# APD9328_ETHERNET.net
KiCad netlist of a schematic drawn in Altium Designer
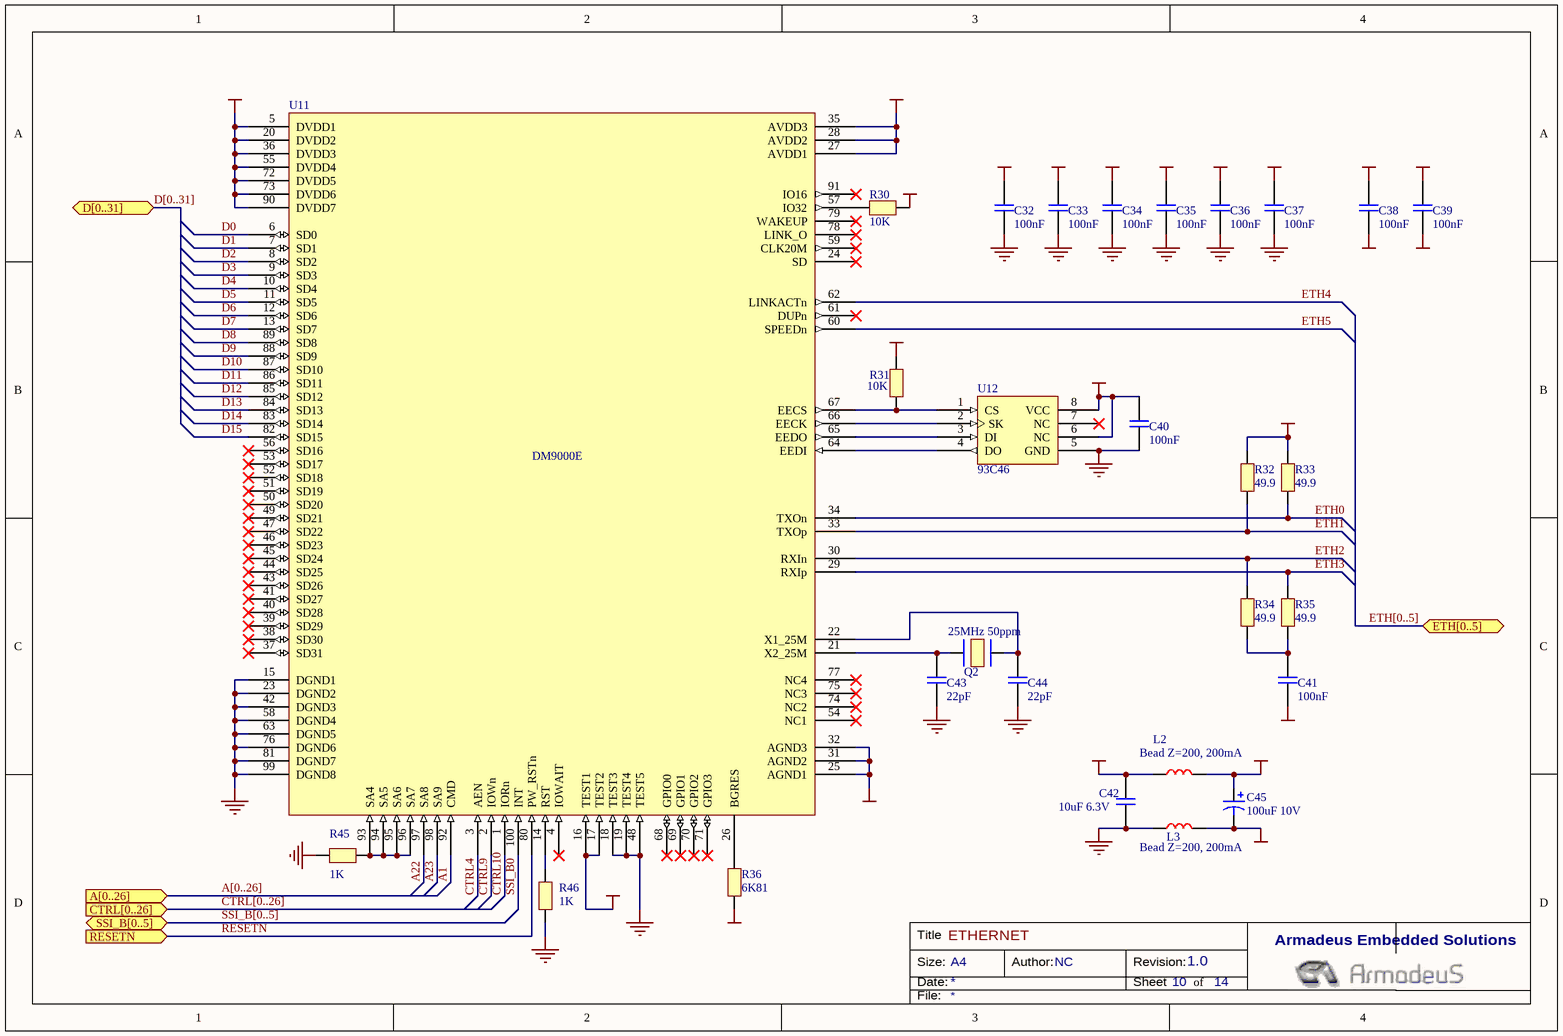
[diagram p0: APD9328_ETHERNET.SchDoc]

(export (version "E")
  (design (tool "Eeschema 10.0.6"))
  (components
    (comp (ref "C32")
      (value "100nF")
      (footprint "0402")
      (fields (field (name "MANUFACTURER") "Kemet") (field (name "PART NUMBER") "C0402C104K8RACTU"))
      (libsource (lib "Misc") (part "Cap"))
    )
    (comp (ref "C33") (value "100nF") (footprint "0402") (libsource (lib "Misc") (part "Cap")))
    (comp (ref "C34") (value "100nF") (footprint "0402") (libsource (lib "Misc") (part "Cap")))
    (comp (ref "C35") (value "100nF") (footprint "0402") (libsource (lib "Misc") (part "Cap")))
    (comp (ref "C36") (value "100nF") (footprint "0402") (libsource (lib "Misc") (part "Cap")))
    (comp (ref "C37") (value "100nF") (footprint "0402") (libsource (lib "Misc") (part "Cap")))
    (comp (ref "C38") (value "100nF") (footprint "0402") (libsource (lib "Misc") (part "Cap")))
    (comp (ref "C39") (value "100nF") (footprint "0402") (libsource (lib "Misc") (part "Cap")))
    (comp (ref "C40") (value "100nF") (footprint "0402") (libsource (lib "Misc") (part "Cap")))
    (comp (ref "C41") (value "100nF") (footprint "0402") (libsource (lib "Misc") (part "Cap")))
    (comp (ref "C42")
      (value "10uF 6.3V")
      (footprint "0805")
      (description "Cermaic Capacitor")
      (fields (field (name "MANUFACTURER") "Kemet") (field (name "PART NUMBER") "C0805C106K9PAC7800"))
      (libsource (lib "Misc") (part "Cap"))
    )
    (comp (ref "C43") (value "22pF") (footprint "0402") (libsource (lib "Misc") (part "Cap")))
    (comp (ref "C44") (value "22pF") (footprint "0402") (libsource (lib "Misc") (part "Cap")))
    (comp (ref "C45")
      (value "100uF 10V")
      (footprint "D")
      (description "Solid Tantalum Chip Capacitor, Standard T491 Series - Industrial Grade")
      (fields
        (field (name "MANUFACTURER") "Kemet")
        (field (name "PART NUMBER") "T491D107K006AS")
        (field (name "PUBLISHER") "Altium Limited")
      )
      (libsource (lib "KEMET Chip Capacitor") (part "T491D"))
    )
    (comp (ref "L2")
      (value "Bead Z=200, 200mA")
      (footprint "0603")
      (description "Bead")
      (fields (field (name "MANUFACTURER") "Murata") (field (name "PART NUMBER") "BLM18AG221SN1"))
      (libsource (lib "*") (part "Self"))
    )
    (comp (ref "L3")
      (value "Bead Z=200, 200mA")
      (footprint "0603")
      (fields (field (name "MANUFACTURER") "Murata") (field (name "PART NUMBER") "BLM18AG221SN1"))
      (libsource (lib "*") (part "Self"))
    )
    (comp (ref "Q2")
      (value "25MHz 50ppm")
      (description "Quartz")
      (fields (field (name "MANUFACTURER") "ECS") (field (name "PART NUMBER") "ECS-250-18-5P"))
      (libsource (lib "*") (part "QUARTZ"))
    )
    (comp (ref "R30") (value "10K") (footprint "0402") (libsource (lib "") (part "Res_2")))
    (comp (ref "R31") (value "10K") (footprint "0402") (libsource (lib "") (part "Res_1")))
    (comp (ref "R32") (value "49.9") (footprint "0402") (libsource (lib "") (part "Res_1")))
    (comp (ref "R33") (value "49.9") (footprint "0402") (libsource (lib "") (part "Res_1")))
    (comp (ref "R34") (value "49.9") (footprint "0402") (libsource (lib "") (part "Res_1")))
    (comp (ref "R35") (value "49.9") (footprint "0402") (libsource (lib "") (part "Res_1")))
    (comp (ref "R36") (value "6K81") (footprint "0402") (libsource (lib "") (part "Res_1")))
    (comp (ref "R45") (value "1K") (footprint "0402") (libsource (lib "*") (part "Res")))
    (comp (ref "R46") (value "1K") (footprint "0402") (libsource (lib "") (part "Res_1")))
    (comp (ref "U11")
      (value "DM9000E")
      (footprint "LQFP100")
      (description "Ethernet Single Chip")
      (fields (field (name "MANUFACTURER") "Davicom"))
      (libsource (lib "Armadeus") (part "DM9000"))
    )
    (comp (ref "U12")
      (value "93C46")
      (footprint "MSOP8")
      (description "Serial Microwire EEPROM")
      (fields (field (name "MANUFACTURER") "Microchip") (field (name "PART NUMBER") "93LC46B-I/MS"))
      (libsource (lib "Armadeus") (part "93C46"))
    )
  )
  (nets
    (net (code "70") (name "+3V3") (class "Default")
      (node (ref "C32") (pin "1") (pintype "passive"))
      (node (ref "C33") (pin "1") (pintype "passive"))
      (node (ref "C34") (pin "1") (pintype "passive"))
      (node (ref "C35") (pin "1") (pintype "passive"))
      (node (ref "C36") (pin "1") (pintype "passive"))
      (node (ref "C37") (pin "1") (pintype "passive"))
      (node (ref "C40") (pin "1") (pintype "passive"))
      (node (ref "C42") (pin "2") (pintype "passive"))
      (node (ref "L2") (pin "1") (pintype "passive"))
      (node (ref "R30") (pin "2") (pintype "passive"))
      (node (ref "R31") (pin "2") (pintype "passive"))
      (node (ref "U11") (pin "16") (pinfunction "TEST1_16") (pintype "input"))
      (node (ref "U11") (pin "17") (pinfunction "TEST2_17") (pintype "input"))
      (node (ref "U11") (pin "20") (pinfunction "DVDD2_20") (pintype "power_in"))
      (node (ref "U11") (pin "36") (pinfunction "DVDD3_36") (pintype "power_in"))
      (node (ref "U11") (pin "5") (pinfunction "DVDD1_5") (pintype "power_in"))
      (node (ref "U11") (pin "55") (pinfunction "DVDD4_55") (pintype "power_in"))
      (node (ref "U11") (pin "72") (pinfunction "DVDD5_72") (pintype "power_in"))
      (node (ref "U11") (pin "73") (pinfunction "DVDD6_73") (pintype "power_in"))
      (node (ref "U11") (pin "90") (pinfunction "DVDD7_90") (pintype "power_in"))
      (node (ref "U12") (pin "6") (pinfunction "NC_6") (pintype "passive"))
      (node (ref "U12") (pin "8") (pinfunction "VCC_8") (pintype "power_in"))
    )
    (net (code "71") (name "/A1") (class "Default")
      (node (ref "U11") (pin "92") (pinfunction "CMD_92") (pintype "input"))
    )
    (net (code "72") (name "/A22") (class "Default")
      (node (ref "U11") (pin "97") (pinfunction "SA8_97") (pintype "input"))
    )
    (net (code "73") (name "/A23") (class "Default")
      (node (ref "U11") (pin "98") (pinfunction "SA9_98") (pintype "input"))
    )
    (net (code "75") (name "/CTRL4") (class "Default")
      (node (ref "U11") (pin "3") (pinfunction "AEN_3") (pintype "input"))
    )
    (net (code "76") (name "/CTRL9") (class "Default")
      (node (ref "U11") (pin "2") (pinfunction "IOWn_2") (pintype "input"))
    )
    (net (code "77") (name "/CTRL10") (class "Default")
      (node (ref "U11") (pin "1") (pinfunction "IORn_1") (pintype "input"))
    )
    (net (code "79") (name "/D0") (class "Default")
      (node (ref "U11") (pin "6") (pinfunction "SD0_6") (pintype "bidirectional"))
    )
    (net (code "80") (name "/D1") (class "Default")
      (node (ref "U11") (pin "7") (pinfunction "SD1_7") (pintype "bidirectional"))
    )
    (net (code "81") (name "/D2") (class "Default")
      (node (ref "U11") (pin "8") (pinfunction "SD2_8") (pintype "bidirectional"))
    )
    (net (code "82") (name "/D3") (class "Default")
      (node (ref "U11") (pin "9") (pinfunction "SD3_9") (pintype "bidirectional"))
    )
    (net (code "83") (name "/D4") (class "Default")
      (node (ref "U11") (pin "10") (pinfunction "SD4_10") (pintype "bidirectional"))
    )
    (net (code "84") (name "/D5") (class "Default")
      (node (ref "U11") (pin "11") (pinfunction "SD5_11") (pintype "bidirectional"))
    )
    (net (code "85") (name "/D6") (class "Default")
      (node (ref "U11") (pin "12") (pinfunction "SD6_12") (pintype "bidirectional"))
    )
    (net (code "86") (name "/D7") (class "Default")
      (node (ref "U11") (pin "13") (pinfunction "SD7_13") (pintype "bidirectional"))
    )
    (net (code "87") (name "/D8") (class "Default")
      (node (ref "U11") (pin "89") (pinfunction "SD8_89") (pintype "bidirectional"))
    )
    (net (code "88") (name "/D9") (class "Default")
      (node (ref "U11") (pin "88") (pinfunction "SD9_88") (pintype "bidirectional"))
    )
    (net (code "89") (name "/D10") (class "Default")
      (node (ref "U11") (pin "87") (pinfunction "SD10_87") (pintype "bidirectional"))
    )
    (net (code "90") (name "/D11") (class "Default")
      (node (ref "U11") (pin "86") (pinfunction "SD11_86") (pintype "bidirectional"))
    )
    (net (code "91") (name "/D12") (class "Default")
      (node (ref "U11") (pin "85") (pinfunction "SD12_85") (pintype "bidirectional"))
    )
    (net (code "92") (name "/D13") (class "Default")
      (node (ref "U11") (pin "84") (pinfunction "SD13_84") (pintype "bidirectional"))
    )
    (net (code "93") (name "/D14") (class "Default")
      (node (ref "U11") (pin "83") (pinfunction "SD14_83") (pintype "bidirectional"))
    )
    (net (code "94") (name "/D15") (class "Default")
      (node (ref "U11") (pin "82") (pinfunction "SD15_82") (pintype "bidirectional"))
    )
    (net (code "96") (name "/ETH0") (class "Default")
      (node (ref "R33") (pin "1") (pintype "passive"))
      (node (ref "U11") (pin "34") (pinfunction "TXOn_34") (pintype "passive"))
    )
    (net (code "97") (name "/ETH1") (class "Default")
      (node (ref "R32") (pin "1") (pintype "passive"))
      (node (ref "U11") (pin "33") (pinfunction "TXOp_33") (pintype "passive"))
    )
    (net (code "98") (name "/ETH2") (class "Default")
      (node (ref "R34") (pin "2") (pintype "passive"))
      (node (ref "U11") (pin "30") (pinfunction "RXIn_30") (pintype "passive"))
    )
    (net (code "99") (name "/ETH3") (class "Default")
      (node (ref "R35") (pin "2") (pintype "passive"))
      (node (ref "U11") (pin "29") (pinfunction "RXIp_29") (pintype "passive"))
    )
    (net (code "100") (name "/ETH4") (class "Default")
      (node (ref "U11") (pin "62") (pinfunction "LINKACTn_62") (pintype "output"))
    )
    (net (code "101") (name "/ETH5") (class "Default")
      (node (ref "U11") (pin "60") (pinfunction "SPEEDn_60") (pintype "output"))
    )
    (net (code "103") (name "/RESETN") (class "Default")
      (node (ref "U11") (pin "80") (pinfunction "PW_RSTn_80") (pintype "input"))
    )
    (net (code "104") (name "/SSI_B0") (class "Default")
      (node (ref "U11") (pin "100") (pinfunction "INT_100") (pintype "input"))
    )
    (net (code "106") (name "AGND") (class "Default")
      (node (ref "C38") (pin "2") (pintype "passive"))
      (node (ref "C39") (pin "2") (pintype "passive"))
      (node (ref "C41") (pin "1") (pintype "passive"))
      (node (ref "C45") (pin "2") (pinfunction "2_2") (pintype "passive"))
      (node (ref "L3") (pin "2") (pintype "passive"))
      (node (ref "R36") (pin "1") (pintype "passive"))
      (node (ref "U11") (pin "25") (pinfunction "AGND1_25") (pintype "power_in"))
      (node (ref "U11") (pin "31") (pinfunction "AGND2_31") (pintype "power_in"))
      (node (ref "U11") (pin "32") (pinfunction "AGND3_32") (pintype "power_in"))
    )
    (net (code "107") (name "AVDD") (class "Default")
      (node (ref "C38") (pin "1") (pintype "passive"))
      (node (ref "C39") (pin "1") (pintype "passive"))
      (node (ref "C45") (pin "1") (pinfunction "1_1") (pintype "passive"))
      (node (ref "L2") (pin "2") (pintype "passive"))
      (node (ref "R32") (pin "2") (pintype "passive"))
      (node (ref "R33") (pin "2") (pintype "passive"))
      (node (ref "U11") (pin "27") (pinfunction "AVDD1_27") (pintype "power_in"))
      (node (ref "U11") (pin "28") (pinfunction "AVDD2_28") (pintype "power_in"))
      (node (ref "U11") (pin "35") (pinfunction "AVDD3_35") (pintype "power_in"))
    )
    (net (code "108") (name "GND") (class "Default")
      (node (ref "C32") (pin "2") (pintype "passive"))
      (node (ref "C33") (pin "2") (pintype "passive"))
      (node (ref "C34") (pin "2") (pintype "passive"))
      (node (ref "C35") (pin "2") (pintype "passive"))
      (node (ref "C36") (pin "2") (pintype "passive"))
      (node (ref "C37") (pin "2") (pintype "passive"))
      (node (ref "C40") (pin "2") (pintype "passive"))
      (node (ref "C42") (pin "1") (pintype "passive"))
      (node (ref "C43") (pin "1") (pintype "passive"))
      (node (ref "C44") (pin "1") (pintype "passive"))
      (node (ref "L3") (pin "1") (pintype "passive"))
      (node (ref "R45") (pin "2") (pintype "passive"))
      (node (ref "R46") (pin "1") (pintype "passive"))
      (node (ref "U11") (pin "15") (pinfunction "DGND1_15") (pintype "power_in"))
      (node (ref "U11") (pin "18") (pinfunction "TEST3_18") (pintype "input"))
      (node (ref "U11") (pin "19") (pinfunction "TEST4_19") (pintype "input"))
      (node (ref "U11") (pin "23") (pinfunction "DGND2_23") (pintype "power_in"))
      (node (ref "U11") (pin "42") (pinfunction "DGND3_42") (pintype "power_in"))
      (node (ref "U11") (pin "48") (pinfunction "TEST5_48") (pintype "input"))
      (node (ref "U11") (pin "58") (pinfunction "DGND4_58") (pintype "power_in"))
      (node (ref "U11") (pin "63") (pinfunction "DGND5_63") (pintype "power_in"))
      (node (ref "U11") (pin "76") (pinfunction "DGND6_76") (pintype "power_in"))
      (node (ref "U11") (pin "81") (pinfunction "DGND7_81") (pintype "power_in"))
      (node (ref "U11") (pin "99") (pinfunction "DGND8_99") (pintype "power_in"))
      (node (ref "U12") (pin "5") (pinfunction "GND_5") (pintype "power_in"))
    )
    (net (code "109") (name "Net-(C41-Pad2)") (class "Default")
      (node (ref "C41") (pin "2") (pintype "passive"))
      (node (ref "R34") (pin "1") (pintype "passive"))
      (node (ref "R35") (pin "1") (pintype "passive"))
    )
    (net (code "110") (name "Net-(U11-BGRES)") (class "Default")
      (node (ref "R36") (pin "2") (pintype "passive"))
      (node (ref "U11") (pin "26") (pinfunction "BGRES_26") (pintype "passive"))
    )
    (net (code "111") (name "Net-(U11-EECK)") (class "Default")
      (node (ref "U11") (pin "66") (pinfunction "EECK_66") (pintype "output"))
      (node (ref "U12") (pin "2") (pinfunction "SK_2") (pintype "input"))
    )
    (net (code "112") (name "Net-(U11-EECS)") (class "Default")
      (node (ref "R31") (pin "1") (pintype "passive"))
      (node (ref "U11") (pin "67") (pinfunction "EECS_67") (pintype "output"))
      (node (ref "U12") (pin "1") (pinfunction "CS_1") (pintype "input"))
    )
    (net (code "113") (name "Net-(U11-EEDI)") (class "Default")
      (node (ref "U11") (pin "64") (pinfunction "EEDI_64") (pintype "input"))
      (node (ref "U12") (pin "4") (pinfunction "DO_4") (pintype "output"))
    )
    (net (code "114") (name "Net-(U11-EEDO)") (class "Default")
      (node (ref "U11") (pin "65") (pinfunction "EEDO_65") (pintype "output"))
      (node (ref "U12") (pin "3") (pinfunction "DI_3") (pintype "input"))
    )
    (net (code "115") (name "Net-(U11-IO32)") (class "Default")
      (node (ref "R30") (pin "1") (pintype "passive"))
      (node (ref "U11") (pin "57") (pinfunction "IO32_57") (pintype "output"))
    )
    (net (code "116") (name "Net-(U11-RST)") (class "Default")
      (node (ref "R46") (pin "2") (pintype "passive"))
      (node (ref "U11") (pin "14") (pinfunction "RST_14") (pintype "input"))
    )
    (net (code "117") (name "Net-(U11-SA4)") (class "Default")
      (node (ref "R45") (pin "1") (pintype "passive"))
      (node (ref "U11") (pin "93") (pinfunction "SA4_93") (pintype "input"))
      (node (ref "U11") (pin "94") (pinfunction "SA5_94") (pintype "input"))
      (node (ref "U11") (pin "95") (pinfunction "SA6_95") (pintype "input"))
      (node (ref "U11") (pin "96") (pinfunction "SA7_96") (pintype "input"))
    )
    (net (code "118") (name "Net-(U11-X1_25M)") (class "Default")
      (node (ref "C44") (pin "2") (pintype "passive"))
      (node (ref "Q2") (pin "2") (pintype "passive"))
      (node (ref "U11") (pin "22") (pinfunction "X1_25M_22") (pintype "passive"))
    )
    (net (code "119") (name "Net-(U11-X2_25M)") (class "Default")
      (node (ref "C43") (pin "2") (pintype "passive"))
      (node (ref "Q2") (pin "1") (pintype "passive"))
      (node (ref "U11") (pin "21") (pinfunction "X2_25M_21") (pintype "passive"))
    )
    (net (code "120") (name "unconnected-(U11-CLK20M-Pad59)") (class "Default")
      (node (ref "U11") (pin "59") (pinfunction "CLK20M_59") (pintype "output+no_connect"))
    )
    (net (code "121") (name "unconnected-(U11-DUPn-Pad61)") (class "Default")
      (node (ref "U11") (pin "61") (pinfunction "DUPn_61") (pintype "output+no_connect"))
    )
    (net (code "122") (name "unconnected-(U11-GPIO0-Pad68)") (class "Default")
      (node (ref "U11") (pin "68") (pinfunction "GPIO0_68") (pintype "bidirectional+no_connect"))
    )
    (net (code "123") (name "unconnected-(U11-GPIO1-Pad69)") (class "Default")
      (node (ref "U11") (pin "69") (pinfunction "GPIO1_69") (pintype "bidirectional+no_connect"))
    )
    (net (code "124") (name "unconnected-(U11-GPIO2-Pad70)") (class "Default")
      (node (ref "U11") (pin "70") (pinfunction "GPIO2_70") (pintype "bidirectional+no_connect"))
    )
    (net (code "125") (name "unconnected-(U11-GPIO3-Pad71)") (class "Default")
      (node (ref "U11") (pin "71") (pinfunction "GPIO3_71") (pintype "bidirectional+no_connect"))
    )
    (net (code "126") (name "unconnected-(U11-IO16-Pad91)") (class "Default")
      (node (ref "U11") (pin "91") (pinfunction "IO16_91") (pintype "output+no_connect"))
    )
    (net (code "127") (name "unconnected-(U11-IOWAIT-Pad4)") (class "Default")
      (node (ref "U11") (pin "4") (pinfunction "IOWAIT_4") (pintype "input+no_connect"))
    )
    (net (code "128") (name "unconnected-(U11-LINK_O-Pad78)") (class "Default")
      (node (ref "U11") (pin "78") (pinfunction "LINK_O_78") (pintype "passive+no_connect"))
    )
    (net (code "129") (name "unconnected-(U11-NC1-Pad54)") (class "Default")
      (node (ref "U11") (pin "54") (pinfunction "NC1_54") (pintype "passive+no_connect"))
    )
    (net (code "130") (name "unconnected-(U11-NC2-Pad74)") (class "Default")
      (node (ref "U11") (pin "74") (pinfunction "NC2_74") (pintype "passive+no_connect"))
    )
    (net (code "131") (name "unconnected-(U11-NC3-Pad75)") (class "Default")
      (node (ref "U11") (pin "75") (pinfunction "NC3_75") (pintype "passive+no_connect"))
    )
    (net (code "132") (name "unconnected-(U11-NC4-Pad77)") (class "Default")
      (node (ref "U11") (pin "77") (pinfunction "NC4_77") (pintype "passive+no_connect"))
    )
    (net (code "133") (name "unconnected-(U11-SD-Pad24)") (class "Default")
      (node (ref "U11") (pin "24") (pinfunction "SD_24") (pintype "passive+no_connect"))
    )
    (net (code "134") (name "unconnected-(U11-SD16-Pad56)") (class "Default")
      (node (ref "U11") (pin "56") (pinfunction "SD16_56") (pintype "bidirectional+no_connect"))
    )
    (net (code "135") (name "unconnected-(U11-SD17-Pad53)") (class "Default")
      (node (ref "U11") (pin "53") (pinfunction "SD17_53") (pintype "bidirectional+no_connect"))
    )
    (net (code "136") (name "unconnected-(U11-SD18-Pad52)") (class "Default")
      (node (ref "U11") (pin "52") (pinfunction "SD18_52") (pintype "bidirectional+no_connect"))
    )
    (net (code "137") (name "unconnected-(U11-SD19-Pad51)") (class "Default")
      (node (ref "U11") (pin "51") (pinfunction "SD19_51") (pintype "bidirectional+no_connect"))
    )
    (net (code "138") (name "unconnected-(U11-SD20-Pad50)") (class "Default")
      (node (ref "U11") (pin "50") (pinfunction "SD20_50") (pintype "bidirectional+no_connect"))
    )
    (net (code "139") (name "unconnected-(U11-SD21-Pad49)") (class "Default")
      (node (ref "U11") (pin "49") (pinfunction "SD21_49") (pintype "bidirectional+no_connect"))
    )
    (net (code "140") (name "unconnected-(U11-SD22-Pad47)") (class "Default")
      (node (ref "U11") (pin "47") (pinfunction "SD22_47") (pintype "bidirectional+no_connect"))
    )
    (net (code "141") (name "unconnected-(U11-SD23-Pad46)") (class "Default")
      (node (ref "U11") (pin "46") (pinfunction "SD23_46") (pintype "bidirectional+no_connect"))
    )
    (net (code "142") (name "unconnected-(U11-SD24-Pad45)") (class "Default")
      (node (ref "U11") (pin "45") (pinfunction "SD24_45") (pintype "bidirectional+no_connect"))
    )
    (net (code "143") (name "unconnected-(U11-SD25-Pad44)") (class "Default")
      (node (ref "U11") (pin "44") (pinfunction "SD25_44") (pintype "bidirectional+no_connect"))
    )
    (net (code "144") (name "unconnected-(U11-SD26-Pad43)") (class "Default")
      (node (ref "U11") (pin "43") (pinfunction "SD26_43") (pintype "bidirectional+no_connect"))
    )
    (net (code "145") (name "unconnected-(U11-SD27-Pad41)") (class "Default")
      (node (ref "U11") (pin "41") (pinfunction "SD27_41") (pintype "bidirectional+no_connect"))
    )
    (net (code "146") (name "unconnected-(U11-SD28-Pad40)") (class "Default")
      (node (ref "U11") (pin "40") (pinfunction "SD28_40") (pintype "bidirectional+no_connect"))
    )
    (net (code "147") (name "unconnected-(U11-SD29-Pad39)") (class "Default")
      (node (ref "U11") (pin "39") (pinfunction "SD29_39") (pintype "bidirectional+no_connect"))
    )
    (net (code "148") (name "unconnected-(U11-SD30-Pad38)") (class "Default")
      (node (ref "U11") (pin "38") (pinfunction "SD30_38") (pintype "bidirectional+no_connect"))
    )
    (net (code "149") (name "unconnected-(U11-SD31-Pad37)") (class "Default")
      (node (ref "U11") (pin "37") (pinfunction "SD31_37") (pintype "bidirectional+no_connect"))
    )
    (net (code "150") (name "unconnected-(U11-WAKEUP-Pad79)") (class "Default")
      (node (ref "U11") (pin "79") (pinfunction "WAKEUP_79") (pintype "passive+no_connect"))
    )
    (net (code "151") (name "unconnected-(U12-NC-Pad7)") (class "Default")
      (node (ref "U12") (pin "7") (pinfunction "NC_7") (pintype "passive+no_connect"))
    )
  )
)
